# SchematicoCombinatore.net
KiCad netlist of a schematic drawn in EAGLE
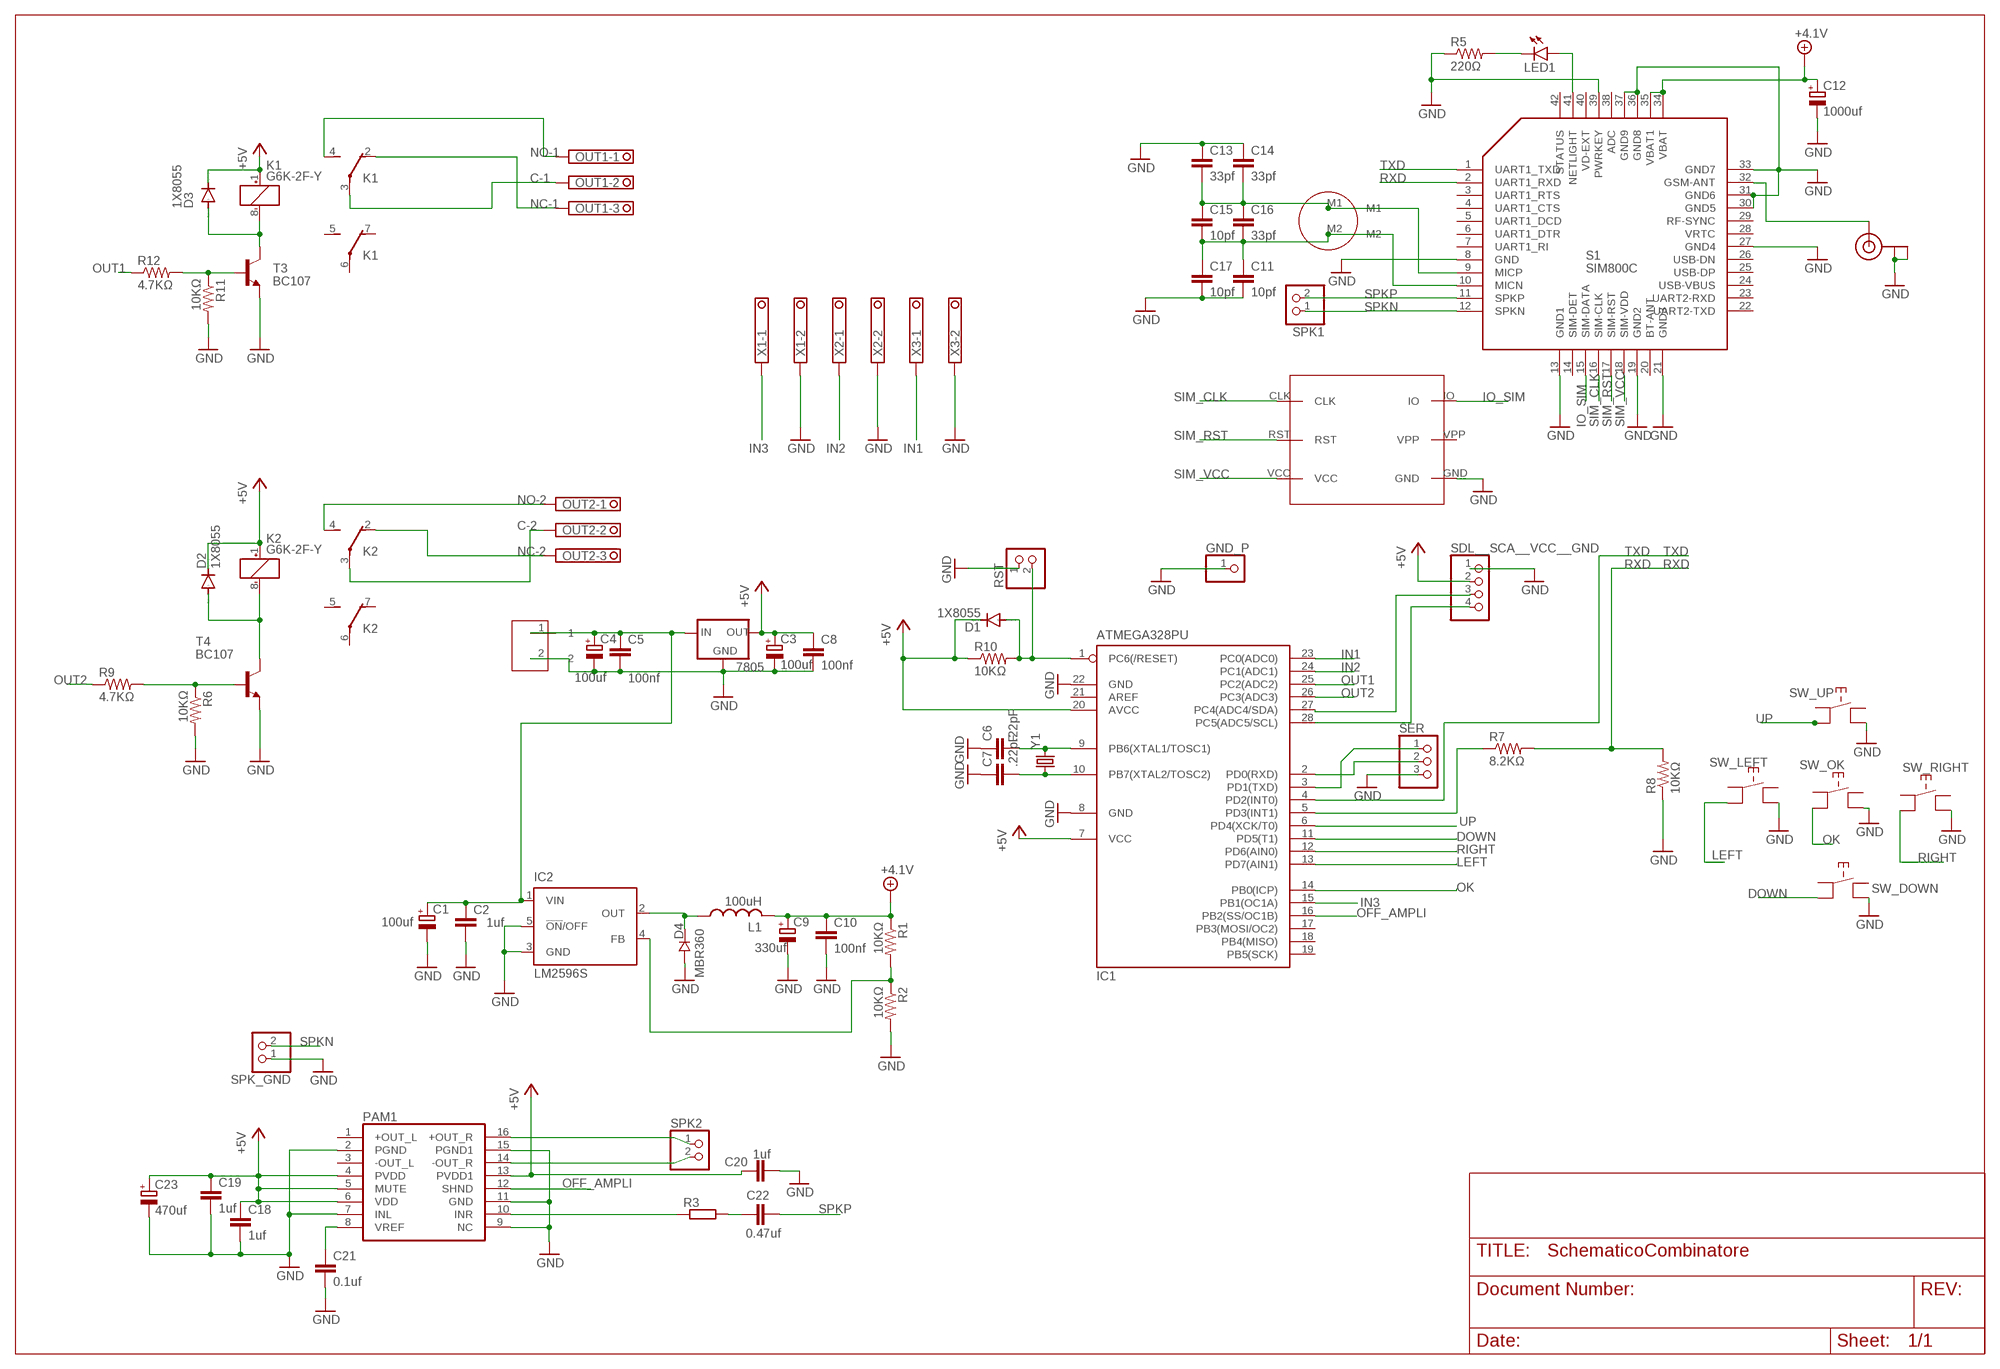
[diagram p0: schematic, sheet 1]

(export (version "E")
  (design (tool "Eeschema 10.0.6"))
  (components
    (comp (ref "7805")
      (value "7805")
      (footprint "eagle-import:78XXL")
      (libsource (lib "eagle-import") (part "V_REG_78XXSIDE"))
    )
    (comp (ref "ALIM")
      (value "CONNETTORE_ALIM")
      (footprint "eagle-import:CONNETTORE_ALIM")
      (libsource (lib "eagle-import") (part "CONNETTORE_ALIM"))
    )
    (comp (ref "C1")
      (value "100uf")
      (footprint "eagle-import:153CLV-0605")
      (libsource (lib "eagle-import") (part "CPOL-EU153CLV-0605"))
    )
    (comp (ref "C2")
      (value "1uf")
      (footprint "eagle-import:C0805")
      (libsource (lib "eagle-import") (part "C-EUC0805"))
    )
    (comp (ref "C3")
      (value "100uf")
      (footprint "eagle-import:153CLV-0605")
      (libsource (lib "eagle-import") (part "CPOL-EU153CLV-0605"))
    )
    (comp (ref "C4")
      (value "100uf")
      (footprint "eagle-import:153CLV-0605")
      (libsource (lib "eagle-import") (part "CPOL-EU153CLV-0605"))
    )
    (comp (ref "C5")
      (value "100nf")
      (footprint "eagle-import:C050-024X044")
      (libsource (lib "eagle-import") (part "C-EU050-024X044"))
    )
    (comp (ref "C6")
      (value ".22pF")
      (footprint "eagle-import:CAP-PTH-SMALL")
      (libsource (lib "eagle-import") (part "CAPPTH"))
    )
    (comp (ref "C7")
      (value ".22pF")
      (footprint "eagle-import:CAP-PTH-SMALL")
      (libsource (lib "eagle-import") (part "CAPPTH"))
    )
    (comp (ref "C8")
      (value "100nf")
      (footprint "eagle-import:C050-024X044")
      (libsource (lib "eagle-import") (part "C-EU050-024X044"))
    )
    (comp (ref "C9")
      (value "330uf")
      (footprint "eagle-import:153CLV-0605")
      (libsource (lib "eagle-import") (part "CPOL-EU153CLV-0605"))
    )
    (comp (ref "C10")
      (value "100nf")
      (footprint "eagle-import:C050-024X044")
      (libsource (lib "eagle-import") (part "C-EU050-024X044"))
    )
    (comp (ref "C11")
      (value "10pf")
      (footprint "eagle-import:C0805")
      (libsource (lib "eagle-import") (part "C-EUC0805"))
    )
    (comp (ref "C12")
      (value "1000uf")
      (footprint "eagle-import:140CLH-1014")
      (libsource (lib "eagle-import") (part "CPOL-EU140CLH-1014"))
    )
    (comp (ref "C13")
      (value "33pf")
      (footprint "eagle-import:C0805")
      (libsource (lib "eagle-import") (part "C-EUC0805"))
    )
    (comp (ref "C14")
      (value "33pf")
      (footprint "eagle-import:C0805")
      (libsource (lib "eagle-import") (part "C-EUC0805"))
    )
    (comp (ref "C15")
      (value "10pf")
      (footprint "eagle-import:C0805")
      (libsource (lib "eagle-import") (part "C-EUC0805"))
    )
    (comp (ref "C16")
      (value "33pf")
      (footprint "eagle-import:C0805")
      (libsource (lib "eagle-import") (part "C-EUC0805"))
    )
    (comp (ref "C17")
      (value "10pf")
      (footprint "eagle-import:C0805")
      (libsource (lib "eagle-import") (part "C-EUC0805"))
    )
    (comp (ref "C18")
      (value "1uf")
      (footprint "eagle-import:C0805")
      (libsource (lib "eagle-import") (part "C-EUC0805"))
    )
    (comp (ref "C19")
      (value "1uf")
      (footprint "eagle-import:C0805")
      (libsource (lib "eagle-import") (part "C-EUC0805"))
    )
    (comp (ref "C20")
      (value "1uf")
      (footprint "eagle-import:C0805")
      (libsource (lib "eagle-import") (part "C-EUC0805"))
    )
    (comp (ref "C21")
      (value "0.1uf")
      (footprint "eagle-import:C0805")
      (libsource (lib "eagle-import") (part "C-EUC0805"))
    )
    (comp (ref "C22")
      (value "0.47uf")
      (footprint "eagle-import:C0805")
      (libsource (lib "eagle-import") (part "C-EUC0805"))
    )
    (comp (ref "C23")
      (value "470uf")
      (footprint "eagle-import:153CLV-0605")
      (libsource (lib "eagle-import") (part "CPOL-EU153CLV-0605"))
    )
    (comp (ref "D1")
      (value "1X8055")
      (footprint "eagle-import:DO41-10")
      (libsource (lib "eagle-import") (part "1N4004"))
    )
    (comp (ref "D2")
      (value "1X8055")
      (footprint "eagle-import:DO41-10")
      (libsource (lib "eagle-import") (part "1N4004"))
    )
    (comp (ref "D3")
      (value "1X8055")
      (footprint "eagle-import:DO41-10")
      (libsource (lib "eagle-import") (part "1N4004"))
    )
    (comp (ref "D4")
      (value "MBR360")
      (footprint "eagle-import:SR360_DIODO_SMD")
      (libsource (lib "eagle-import") (part "MBR360"))
    )
    (comp (ref "GND_P")
      (value "PINHD-1X1")
      (footprint "eagle-import:1X01")
      (libsource (lib "eagle-import") (part "PINHD-1X1"))
    )
    (comp (ref "IC1")
      (value "ATMEGA328PU")
      (footprint "eagle-import:DIL28-3")
      (libsource (lib "eagle-import") (part "MEGA8-P"))
    )
    (comp (ref "IC2")
      (value "LM2596S")
      (footprint "eagle-import:TO263-5")
      (fields (field (name "MF") "NATIONAL SEMICONDUCTOR") (field (name "MPN") "LM2596S-ADJ/NOPB"))
      (libsource (lib "eagle-import") (part "LM2596S"))
    )
    (comp (ref "K1")
      (value "G6K-2F-Y")
      (footprint "eagle-import:G6K-2F-Y")
      (fields (field (name "MF") "OMRON COMPONENTS USA") (field (name "MPN") "G6K-2F-Y DC3"))
      (libsource (lib "eagle-import") (part "G6K-2F-Y"))
    )
    (comp (ref "K2")
      (value "G6K-2F-Y")
      (footprint "eagle-import:G6K-2F-Y")
      (fields (field (name "MF") "OMRON COMPONENTS USA") (field (name "MPN") "G6K-2F-Y DC3"))
      (libsource (lib "eagle-import") (part "G6K-2F-Y"))
    )
    (comp (ref "L1")
      (value "100uH")
      (footprint "eagle-import:0204_7")
      (libsource (lib "eagle-import") (part "L-US0204/7"))
    )
    (comp (ref "LED1")
      (value "LED3MM")
      (footprint "eagle-import:LED3MM")
      (libsource (lib "eagle-import") (part "LED3MM"))
    )
    (comp (ref "MIC2")
      (value "MICROPHONE")
      (footprint "eagle-import:MICROFONO1")
      (libsource (lib "eagle-import") (part "MICROPHONE"))
    )
    (comp (ref "OUT1")
      (value "1751251")
      (footprint "eagle-import:1751251")
      (libsource (lib "eagle-import") (part "1751251"))
    )
    (comp (ref "OUT2")
      (value "NC")
      (footprint "eagle-import:1751251")
      (libsource (lib "eagle-import") (part "1751251"))
    )
    (comp (ref "PAM1")
      (value "PAM8403")
      (footprint "eagle-import:SOP-16")
      (libsource (lib "eagle-import") (part "PAM8403"))
    )
    (comp (ref "R1")
      (value "10KΩ")
      (footprint "eagle-import:0402-RES")
      (libsource (lib "eagle-import") (part "RESISTOR0402-RES"))
    )
    (comp (ref "R2")
      (value "10KΩ")
      (footprint "eagle-import:0402-RES")
      (libsource (lib "eagle-import") (part "RESISTOR0402-RES"))
    )
    (comp (ref "R3")
      (value "R-EU_R0402")
      (footprint "eagle-import:R0402")
      (libsource (lib "eagle-import") (part "R-EU_R0402"))
    )
    (comp (ref "R5")
      (value "220Ω")
      (footprint "eagle-import:0402-RES")
      (libsource (lib "eagle-import") (part "RESISTOR0402-RES"))
    )
    (comp (ref "R6")
      (value "10KΩ")
      (footprint "eagle-import:0402-RES")
      (libsource (lib "eagle-import") (part "RESISTOR0402-RES"))
    )
    (comp (ref "R7")
      (value "8.2KΩ")
      (footprint "eagle-import:0402-RES")
      (libsource (lib "eagle-import") (part "RESISTOR0402-RES"))
    )
    (comp (ref "R8")
      (value "10KΩ")
      (footprint "eagle-import:0402-RES")
      (libsource (lib "eagle-import") (part "RESISTOR0402-RES"))
    )
    (comp (ref "R9")
      (value "4.7KΩ")
      (footprint "eagle-import:0402-RES")
      (libsource (lib "eagle-import") (part "RESISTOR0402-RES"))
    )
    (comp (ref "R10")
      (value "10KΩ")
      (footprint "eagle-import:0402-RES")
      (libsource (lib "eagle-import") (part "RESISTOR0402-RES"))
    )
    (comp (ref "R11")
      (value "10KΩ")
      (footprint "eagle-import:0402-RES")
      (libsource (lib "eagle-import") (part "RESISTOR0402-RES"))
    )
    (comp (ref "R12")
      (value "4.7KΩ")
      (footprint "eagle-import:0402-RES")
      (libsource (lib "eagle-import") (part "RESISTOR0402-RES"))
    )
    (comp (ref "RST")
      (value "PINHD-1X2")
      (footprint "eagle-import:1X02")
      (libsource (lib "eagle-import") (part "PINHD-1X2"))
    )
    (comp (ref "S1")
      (value "SIM800C")
      (footprint "eagle-import:SIM800C")
      (libsource (lib "eagle-import") (part "SIM800C"))
    )
    (comp (ref "SDL__SCA__VCC__GND")
      (value "PINHD-1X4")
      (footprint "eagle-import:1X04")
      (libsource (lib "eagle-import") (part "PINHD-1X4"))
    )
    (comp (ref "SER")
      (value "PINHD-1X3")
      (footprint "eagle-import:1X03")
      (libsource (lib "eagle-import") (part "PINHD-1X3"))
    )
    (comp (ref "SPK1")
      (value "PINHD-1X2")
      (footprint "eagle-import:1X02")
      (libsource (lib "eagle-import") (part "PINHD-1X2"))
    )
    (comp (ref "SPK2")
      (value "PINHD-1X2")
      (footprint "eagle-import:1X02")
      (libsource (lib "eagle-import") (part "PINHD-1X2"))
    )
    (comp (ref "SPK_GND")
      (value "PINHD-1X2")
      (footprint "eagle-import:1X02")
      (libsource (lib "eagle-import") (part "PINHD-1X2"))
    )
    (comp (ref "SW_DOWN")
      (value "PULSANTE_DIP_SWITCH")
      (footprint "eagle-import:PULSANTE_DIP_SWITCH")
      (libsource (lib "eagle-import") (part "PULSANTE_DIP_SWITCH"))
    )
    (comp (ref "SW_LEFT")
      (value "PULSANTE_DIP_SWITCH")
      (footprint "eagle-import:PULSANTE_DIP_SWITCH")
      (libsource (lib "eagle-import") (part "PULSANTE_DIP_SWITCH"))
    )
    (comp (ref "SW_OK")
      (value "PULSANTE_DIP_SWITCH")
      (footprint "eagle-import:PULSANTE_DIP_SWITCH")
      (libsource (lib "eagle-import") (part "PULSANTE_DIP_SWITCH"))
    )
    (comp (ref "SW_RIGHT")
      (value "PULSANTE_DIP_SWITCH")
      (footprint "eagle-import:PULSANTE_DIP_SWITCH")
      (libsource (lib "eagle-import") (part "PULSANTE_DIP_SWITCH"))
    )
    (comp (ref "SW_UP")
      (value "PULSANTE_DIP_SWITCH")
      (footprint "eagle-import:PULSANTE_DIP_SWITCH")
      (libsource (lib "eagle-import") (part "PULSANTE_DIP_SWITCH"))
    )
    (comp (ref "T3")
      (value "BC107")
      (footprint "eagle-import:TO18")
      (libsource (lib "eagle-import") (part "BC107"))
    )
    (comp (ref "T4")
      (value "BC107")
      (footprint "eagle-import:TO18")
      (libsource (lib "eagle-import") (part "BC107"))
    )
    (comp (ref "U$1")
      (value "U.FL")
      (footprint "eagle-import:U.FL")
      (libsource (lib "eagle-import") (part "U.FL"))
    )
    (comp (ref "U$2")
      (value "NANO_SIM_CARD_HOLDER")
      (footprint "eagle-import:NANO_SIM_CARD_HOLDER")
      (libsource (lib "eagle-import") (part "NANO_SIM_CARD_HOLDER"))
    )
    (comp (ref "X1")
      (value "1751248")
      (footprint "eagle-import:1751248")
      (libsource (lib "eagle-import") (part "1751248"))
    )
    (comp (ref "X2")
      (value "1751248")
      (footprint "eagle-import:1751248")
      (libsource (lib "eagle-import") (part "1751248"))
    )
    (comp (ref "X3")
      (value "1751248")
      (footprint "eagle-import:1751248")
      (libsource (lib "eagle-import") (part "1751248"))
    )
    (comp (ref "Y1")
      (value "CRYSTALHC49US")
      (footprint "eagle-import:HC49US")
      (libsource (lib "eagle-import") (part "CRYSTALHC49US"))
    )
  )
  (nets
    (net (code "1") (name "+4.1V") (class "Default")
      (node (ref "C10") (pin "1") (pinfunction "1_1") (pintype "passive"))
      (node (ref "C12") (pin "+") (pinfunction "+_+") (pintype "passive"))
      (node (ref "C9") (pin "+") (pinfunction "+_+") (pintype "passive"))
      (node (ref "L1") (pin "2") (pinfunction "2_2") (pintype "passive"))
      (node (ref "R1") (pin "1") (pinfunction "1_1") (pintype "passive"))
      (node (ref "S1") (pin "34") (pinfunction "VBAT_34") (pintype "power_in"))
      (node (ref "S1") (pin "35") (pinfunction "VBAT1_35") (pintype "power_in"))
    )
    (net (code "2") (name "+5V") (class "Default")
      (node (ref "7805") (pin "OUT") (pinfunction "OUT_OUT") (pintype "output"))
      (node (ref "C18") (pin "1") (pinfunction "1_1") (pintype "passive"))
      (node (ref "C19") (pin "1") (pinfunction "1_1") (pintype "passive"))
      (node (ref "C20") (pin "1") (pinfunction "1_1") (pintype "passive"))
      (node (ref "C23") (pin "+") (pinfunction "+_+") (pintype "passive"))
      (node (ref "C3") (pin "+") (pinfunction "+_+") (pintype "passive"))
      (node (ref "C8") (pin "1") (pinfunction "1_1") (pintype "passive"))
      (node (ref "D1") (pin "C") (pinfunction "C_C") (pintype "passive"))
      (node (ref "D2") (pin "C") (pinfunction "C_C") (pintype "passive"))
      (node (ref "D3") (pin "C") (pinfunction "C_C") (pintype "passive"))
      (node (ref "IC1") (pin "20") (pinfunction "AVCC_20") (pintype "power_in"))
      (node (ref "IC1") (pin "7") (pinfunction "VCC_7") (pintype "power_in"))
      (node (ref "K1") (pin "1") (pinfunction "+_1") (pintype "passive"))
      (node (ref "K2") (pin "1") (pinfunction "+_1") (pintype "passive"))
      (node (ref "PAM1") (pin "13") (pinfunction "PVDD1_13") (pintype "output"))
      (node (ref "PAM1") (pin "4") (pinfunction "PVDD_4") (pintype "input"))
      (node (ref "PAM1") (pin "5") (pinfunction "MUTE_5") (pintype "input"))
      (node (ref "PAM1") (pin "6") (pinfunction "VDD_6") (pintype "input"))
      (node (ref "R10") (pin "1") (pinfunction "1_1") (pintype "passive"))
      (node (ref "SDL__SCA__VCC__GND") (pin "2") (pinfunction "2_2") (pintype "passive"))
    )
    (net (code "3") (name "/C-1") (class "Default")
      (node (ref "K1") (pin "3") (pinfunction "P_3") (pintype "passive"))
      (node (ref "OUT1") (pin "2") (pinfunction "K_2") (pintype "passive"))
    )
    (net (code "4") (name "/C-2") (class "Default")
      (node (ref "K2") (pin "3") (pinfunction "P_3") (pintype "passive"))
      (node (ref "OUT2") (pin "2") (pinfunction "K_2") (pintype "passive"))
    )
    (net (code "5") (name "/DOWN") (class "Default")
      (node (ref "IC1") (pin "11") (pinfunction "PD5(T1)_11") (pintype "bidirectional"))
      (node (ref "SW_DOWN") (pin "3") (pinfunction "2_3") (pintype "bidirectional"))
    )
    (net (code "6") (name "/IN1") (class "Default")
      (node (ref "IC1") (pin "23") (pinfunction "PC0(ADC0)_23") (pintype "bidirectional"))
      (node (ref "X3") (pin "1") (pinfunction "K_1") (pintype "passive"))
    )
    (net (code "7") (name "/IN2") (class "Default")
      (node (ref "IC1") (pin "24") (pinfunction "PC1(ADC1)_24") (pintype "bidirectional"))
      (node (ref "X2") (pin "1") (pinfunction "K_1") (pintype "passive"))
    )
    (net (code "8") (name "/IN3") (class "Default")
      (node (ref "IC1") (pin "15") (pinfunction "PB1(OC1A)_15") (pintype "bidirectional"))
      (node (ref "X1") (pin "1") (pinfunction "K_1") (pintype "passive"))
    )
    (net (code "9") (name "/IO_SIM") (class "Default")
      (node (ref "S1") (pin "15") (pinfunction "SIM-DATA_15") (pintype "bidirectional"))
      (node (ref "U$2") (pin "IO") (pinfunction "IO_IO") (pintype "bidirectional"))
    )
    (net (code "10") (name "/LEFT") (class "Default")
      (node (ref "IC1") (pin "13") (pinfunction "PD7(AIN1)_13") (pintype "bidirectional"))
      (node (ref "SW_LEFT") (pin "3") (pinfunction "2_3") (pintype "bidirectional"))
    )
    (net (code "11") (name "/NC-1") (class "Default")
      (node (ref "K1") (pin "2") (pinfunction "O_2") (pintype "passive"))
      (node (ref "OUT1") (pin "3") (pinfunction "K_3") (pintype "passive"))
    )
    (net (code "12") (name "/NC-2") (class "Default")
      (node (ref "K2") (pin "2") (pinfunction "O_2") (pintype "passive"))
      (node (ref "OUT2") (pin "3") (pinfunction "K_3") (pintype "passive"))
    )
    (net (code "13") (name "/NO-1") (class "Default")
      (node (ref "K1") (pin "4") (pinfunction "S_4") (pintype "passive"))
      (node (ref "OUT1") (pin "1") (pinfunction "K_1") (pintype "passive"))
    )
    (net (code "14") (name "/NO-2") (class "Default")
      (node (ref "K2") (pin "4") (pinfunction "S_4") (pintype "passive"))
      (node (ref "OUT2") (pin "1") (pinfunction "K_1") (pintype "passive"))
    )
    (net (code "15") (name "/OFF_AMPLI") (class "Default")
      (node (ref "IC1") (pin "16") (pinfunction "PB2(SS/OC1B)_16") (pintype "bidirectional"))
      (node (ref "PAM1") (pin "12") (pinfunction "SHND_12") (pintype "output"))
    )
    (net (code "16") (name "/OK") (class "Default")
      (node (ref "IC1") (pin "14") (pinfunction "PB0(ICP)_14") (pintype "bidirectional"))
      (node (ref "SW_OK") (pin "3") (pinfunction "2_3") (pintype "bidirectional"))
    )
    (net (code "17") (name "/OUT1") (class "Default")
      (node (ref "IC1") (pin "25") (pinfunction "PC2(ADC2)_25") (pintype "bidirectional"))
      (node (ref "R12") (pin "1") (pinfunction "1_1") (pintype "passive"))
    )
    (net (code "18") (name "/OUT2") (class "Default")
      (node (ref "IC1") (pin "26") (pinfunction "PC3(ADC3)_26") (pintype "bidirectional"))
      (node (ref "R9") (pin "1") (pinfunction "1_1") (pintype "passive"))
    )
    (net (code "19") (name "/RIGHT") (class "Default")
      (node (ref "IC1") (pin "12") (pinfunction "PD6(AIN0)_12") (pintype "bidirectional"))
      (node (ref "SW_RIGHT") (pin "3") (pinfunction "2_3") (pintype "bidirectional"))
    )
    (net (code "20") (name "/RXD") (class "Default")
      (node (ref "R7") (pin "2") (pinfunction "2_2") (pintype "passive"))
      (node (ref "R8") (pin "2") (pinfunction "2_2") (pintype "passive"))
      (node (ref "S1") (pin "2") (pinfunction "UART1_RXD_2") (pintype "bidirectional"))
    )
    (net (code "21") (name "/SIM_CLK") (class "Default")
      (node (ref "S1") (pin "16") (pinfunction "SIM-CLK_16") (pintype "bidirectional"))
      (node (ref "U$2") (pin "CLK") (pinfunction "CLK_CLK") (pintype "bidirectional"))
    )
    (net (code "22") (name "/SIM_RST") (class "Default")
      (node (ref "S1") (pin "17") (pinfunction "SIM-RST_17") (pintype "bidirectional"))
      (node (ref "U$2") (pin "RST") (pinfunction "RST_RST") (pintype "bidirectional"))
    )
    (net (code "23") (name "/SIM_VCC") (class "Default")
      (node (ref "S1") (pin "18") (pinfunction "SIM-VDD_18") (pintype "bidirectional"))
      (node (ref "U$2") (pin "VCC") (pinfunction "VCC_VCC") (pintype "bidirectional"))
    )
    (net (code "24") (name "/SPKN") (class "Default")
      (node (ref "S1") (pin "12") (pinfunction "SPKN_12") (pintype "bidirectional"))
      (node (ref "SPK1") (pin "1") (pinfunction "1_1") (pintype "passive"))
      (node (ref "SPK_GND") (pin "2") (pinfunction "2_2") (pintype "passive"))
    )
    (net (code "25") (name "/SPKP") (class "Default")
      (node (ref "C22") (pin "2") (pinfunction "2_2") (pintype "passive"))
      (node (ref "S1") (pin "11") (pinfunction "SPKP_11") (pintype "bidirectional"))
      (node (ref "SPK1") (pin "2") (pinfunction "2_2") (pintype "passive"))
    )
    (net (code "26") (name "/TXD") (class "Default")
      (node (ref "IC1") (pin "4") (pinfunction "PD2(INT0)_4") (pintype "bidirectional"))
      (node (ref "S1") (pin "1") (pinfunction "UART1_TXD_1") (pintype "bidirectional"))
    )
    (net (code "27") (name "/UP") (class "Default")
      (node (ref "IC1") (pin "6") (pinfunction "PD4(XCK/T0)_6") (pintype "bidirectional"))
      (node (ref "SW_UP") (pin "3") (pinfunction "2_3") (pintype "bidirectional"))
    )
    (net (code "28") (name "GND") (class "Default")
      (node (ref "7805") (pin "GND") (pinfunction "GND_GND") (pintype "input"))
      (node (ref "ALIM") (pin "2") (pinfunction "2_2") (pintype "bidirectional"))
      (node (ref "C1") (pin "-") (pinfunction "-_-") (pintype "passive"))
      (node (ref "C10") (pin "2") (pinfunction "2_2") (pintype "passive"))
      (node (ref "C11") (pin "2") (pinfunction "2_2") (pintype "passive"))
      (node (ref "C12") (pin "-") (pinfunction "-_-") (pintype "passive"))
      (node (ref "C13") (pin "1") (pinfunction "1_1") (pintype "passive"))
      (node (ref "C14") (pin "1") (pinfunction "1_1") (pintype "passive"))
      (node (ref "C17") (pin "2") (pinfunction "2_2") (pintype "passive"))
      (node (ref "C18") (pin "2") (pinfunction "2_2") (pintype "passive"))
      (node (ref "C19") (pin "2") (pinfunction "2_2") (pintype "passive"))
      (node (ref "C2") (pin "2") (pinfunction "2_2") (pintype "passive"))
      (node (ref "C20") (pin "2") (pinfunction "2_2") (pintype "passive"))
      (node (ref "C21") (pin "2") (pinfunction "2_2") (pintype "passive"))
      (node (ref "C23") (pin "-") (pinfunction "-_-") (pintype "passive"))
      (node (ref "C3") (pin "-") (pinfunction "-_-") (pintype "passive"))
      (node (ref "C4") (pin "-") (pinfunction "-_-") (pintype "passive"))
      (node (ref "C5") (pin "2") (pinfunction "2_2") (pintype "passive"))
      (node (ref "C6") (pin "1") (pinfunction "1_1") (pintype "passive"))
      (node (ref "C7") (pin "1") (pinfunction "1_1") (pintype "passive"))
      (node (ref "C8") (pin "2") (pinfunction "2_2") (pintype "passive"))
      (node (ref "C9") (pin "-") (pinfunction "-_-") (pintype "passive"))
      (node (ref "D4") (pin "P$1") (pinfunction "P$1_P$1") (pintype "bidirectional"))
      (node (ref "GND_P") (pin "1") (pinfunction "1_1") (pintype "passive"))
      (node (ref "IC1") (pin "22") (pinfunction "GND_22") (pintype "power_in"))
      (node (ref "IC1") (pin "8") (pinfunction "GND_8") (pintype "power_in"))
      (node (ref "IC2") (pin "3") (pinfunction "GND_3") (pintype "power_in"))
      (node (ref "IC2") (pin "5") (pinfunction "~{ON}/OFF_5") (pintype "input"))
      (node (ref "PAM1") (pin "11") (pinfunction "GND_11") (pintype "output"))
      (node (ref "PAM1") (pin "15") (pinfunction "PGND1_15") (pintype "output"))
      (node (ref "PAM1") (pin "2") (pinfunction "PGND_2") (pintype "input"))
      (node (ref "PAM1") (pin "7") (pinfunction "INL_7") (pintype "input"))
      (node (ref "PAM1") (pin "9") (pinfunction "NC_9") (pintype "output"))
      (node (ref "R11") (pin "2") (pinfunction "2_2") (pintype "passive"))
      (node (ref "R2") (pin "2") (pinfunction "2_2") (pintype "passive"))
      (node (ref "R5") (pin "1") (pinfunction "1_1") (pintype "passive"))
      (node (ref "R6") (pin "2") (pinfunction "2_2") (pintype "passive"))
      (node (ref "R8") (pin "1") (pinfunction "1_1") (pintype "passive"))
      (node (ref "RST") (pin "1") (pinfunction "1_1") (pintype "passive"))
      (node (ref "S1") (pin "13") (pinfunction "GND1_13") (pintype "power_in"))
      (node (ref "S1") (pin "19") (pinfunction "GND2_19") (pintype "power_in"))
      (node (ref "S1") (pin "21") (pinfunction "GND3_21") (pintype "power_in"))
      (node (ref "S1") (pin "27") (pinfunction "GND4_27") (pintype "power_in"))
      (node (ref "S1") (pin "30") (pinfunction "GND5_30") (pintype "power_in"))
      (node (ref "S1") (pin "31") (pinfunction "GND6_31") (pintype "power_in"))
      (node (ref "S1") (pin "33") (pinfunction "GND7_33") (pintype "power_in"))
      (node (ref "S1") (pin "36") (pinfunction "GND8_36") (pintype "power_in"))
      (node (ref "S1") (pin "37") (pinfunction "GND9_37") (pintype "power_in"))
      (node (ref "S1") (pin "39") (pinfunction "PWRKEY_39") (pintype "bidirectional"))
      (node (ref "S1") (pin "8") (pinfunction "GND_8") (pintype "power_in"))
      (node (ref "SDL__SCA__VCC__GND") (pin "1") (pinfunction "1_1") (pintype "passive"))
      (node (ref "SER") (pin "3") (pinfunction "3_3") (pintype "passive"))
      (node (ref "SPK_GND") (pin "1") (pinfunction "1_1") (pintype "passive"))
      (node (ref "SW_DOWN") (pin "1") (pinfunction "4_1") (pintype "bidirectional"))
      (node (ref "SW_LEFT") (pin "1") (pinfunction "4_1") (pintype "bidirectional"))
      (node (ref "SW_OK") (pin "1") (pinfunction "4_1") (pintype "bidirectional"))
      (node (ref "SW_RIGHT") (pin "1") (pinfunction "4_1") (pintype "bidirectional"))
      (node (ref "SW_UP") (pin "1") (pinfunction "4_1") (pintype "bidirectional"))
      (node (ref "T3") (pin "1") (pinfunction "E_1") (pintype "passive"))
      (node (ref "T4") (pin "1") (pinfunction "E_1") (pintype "passive"))
      (node (ref "U$1") (pin "1") (pinfunction "GND_1") (pintype "passive"))
      (node (ref "U$1") (pin "2") (pinfunction "GND_2") (pintype "passive"))
      (node (ref "U$2") (pin "GND") (pinfunction "GND_GND") (pintype "bidirectional"))
      (node (ref "X1") (pin "2") (pinfunction "K_2") (pintype "passive"))
      (node (ref "X2") (pin "2") (pinfunction "K_2") (pintype "passive"))
      (node (ref "X3") (pin "2") (pinfunction "K_2") (pintype "passive"))
    )
    (net (code "29") (name "Net-(C22-Pad1)") (class "Default")
      (node (ref "C22") (pin "1") (pinfunction "1_1") (pintype "passive"))
      (node (ref "R3") (pin "2") (pinfunction "2_2") (pintype "passive"))
    )
    (net (code "30") (name "Net-(IC1-PB6(XTAL1{slash}TOSC1))") (class "Default")
      (node (ref "C6") (pin "2") (pinfunction "2_2") (pintype "passive"))
      (node (ref "IC1") (pin "9") (pinfunction "PB6(XTAL1/TOSC1)_9") (pintype "bidirectional"))
      (node (ref "Y1") (pin "2") (pinfunction "2_2") (pintype "passive"))
    )
    (net (code "31") (name "Net-(IC1-PB7(XTAL2{slash}TOSC2))") (class "Default")
      (node (ref "C7") (pin "2") (pinfunction "2_2") (pintype "passive"))
      (node (ref "IC1") (pin "10") (pinfunction "PB7(XTAL2/TOSC2)_10") (pintype "bidirectional"))
      (node (ref "Y1") (pin "1") (pinfunction "1_1") (pintype "passive"))
    )
    (net (code "32") (name "Net-(IC1-PC4(ADC4{slash}SDA))") (class "Default")
      (node (ref "IC1") (pin "27") (pinfunction "PC4(ADC4/SDA)_27") (pintype "bidirectional"))
      (node (ref "SDL__SCA__VCC__GND") (pin "3") (pinfunction "3_3") (pintype "passive"))
    )
    (net (code "33") (name "Net-(IC1-PC5(ADC5{slash}SCL))") (class "Default")
      (node (ref "IC1") (pin "28") (pinfunction "PC5(ADC5/SCL)_28") (pintype "bidirectional"))
      (node (ref "SDL__SCA__VCC__GND") (pin "4") (pinfunction "4_4") (pintype "passive"))
    )
    (net (code "34") (name "Net-(IC1-PC6({slash}RESET))") (class "Default")
      (node (ref "D1") (pin "A") (pinfunction "A_A") (pintype "passive"))
      (node (ref "IC1") (pin "1") (pinfunction "PC6(/RESET)_1") (pintype "bidirectional"))
      (node (ref "R10") (pin "2") (pinfunction "2_2") (pintype "passive"))
      (node (ref "RST") (pin "2") (pinfunction "2_2") (pintype "passive"))
    )
    (net (code "35") (name "Net-(IC1-PD0(RXD))") (class "Default")
      (node (ref "IC1") (pin "2") (pinfunction "PD0(RXD)_2") (pintype "bidirectional"))
      (node (ref "SER") (pin "2") (pinfunction "2_2") (pintype "passive"))
    )
    (net (code "36") (name "Net-(IC1-PD1(TXD))") (class "Default")
      (node (ref "IC1") (pin "3") (pinfunction "PD1(TXD)_3") (pintype "bidirectional"))
      (node (ref "SER") (pin "1") (pinfunction "1_1") (pintype "passive"))
    )
    (net (code "37") (name "Net-(IC1-PD3(INT1))") (class "Default")
      (node (ref "IC1") (pin "5") (pinfunction "PD3(INT1)_5") (pintype "bidirectional"))
      (node (ref "R7") (pin "1") (pinfunction "1_1") (pintype "passive"))
    )
    (net (code "38") (name "Net-(IC2-FB)") (class "Default")
      (node (ref "IC2") (pin "4") (pinfunction "FB_4") (pintype "input"))
      (node (ref "R1") (pin "2") (pinfunction "2_2") (pintype "passive"))
      (node (ref "R2") (pin "1") (pinfunction "1_1") (pintype "passive"))
    )
    (net (code "39") (name "Net-(IC2-OUT)") (class "Default")
      (node (ref "D4") (pin "P$2") (pinfunction "P$2_P$2") (pintype "bidirectional"))
      (node (ref "IC2") (pin "2") (pinfunction "OUT_2") (pintype "output"))
      (node (ref "L1") (pin "1") (pinfunction "1_1") (pintype "passive"))
    )
    (net (code "40") (name "Net-(IC2-VIN)") (class "Default")
      (node (ref "7805") (pin "IN") (pinfunction "IN_IN") (pintype "input"))
      (node (ref "ALIM") (pin "1") (pinfunction "1_1") (pintype "bidirectional"))
      (node (ref "C1") (pin "+") (pinfunction "+_+") (pintype "passive"))
      (node (ref "C2") (pin "1") (pinfunction "1_1") (pintype "passive"))
      (node (ref "C4") (pin "+") (pinfunction "+_+") (pintype "passive"))
      (node (ref "C5") (pin "1") (pinfunction "1_1") (pintype "passive"))
      (node (ref "IC2") (pin "1") (pinfunction "VIN_1") (pintype "input"))
    )
    (net (code "41") (name "Net-(K1A--)") (class "Default")
      (node (ref "D3") (pin "A") (pinfunction "A_A") (pintype "passive"))
      (node (ref "K1") (pin "8") (pinfunction "-_8") (pintype "passive"))
      (node (ref "T3") (pin "3") (pinfunction "C_3") (pintype "passive"))
    )
    (net (code "42") (name "Net-(K2A--)") (class "Default")
      (node (ref "D2") (pin "A") (pinfunction "A_A") (pintype "passive"))
      (node (ref "K2") (pin "8") (pinfunction "-_8") (pintype "passive"))
      (node (ref "T4") (pin "3") (pinfunction "C_3") (pintype "passive"))
    )
    (net (code "43") (name "Net-(LED1-C)") (class "Default")
      (node (ref "LED1") (pin "K") (pinfunction "C_K") (pintype "passive"))
      (node (ref "R5") (pin "2") (pinfunction "2_2") (pintype "passive"))
    )
    (net (code "44") (name "Net-(PAM1-+OUT_R)") (class "Default")
      (node (ref "PAM1") (pin "16") (pinfunction "+OUT_R_16") (pintype "output"))
      (node (ref "SPK2") (pin "1") (pinfunction "1_1") (pintype "passive"))
    )
    (net (code "45") (name "Net-(PAM1--OUT_R)") (class "Default")
      (node (ref "PAM1") (pin "14") (pinfunction "-OUT_R_14") (pintype "output"))
      (node (ref "SPK2") (pin "2") (pinfunction "2_2") (pintype "passive"))
    )
    (net (code "46") (name "Net-(PAM1-INR)") (class "Default")
      (node (ref "PAM1") (pin "10") (pinfunction "INR_10") (pintype "output"))
      (node (ref "R3") (pin "1") (pinfunction "1_1") (pintype "passive"))
    )
    (net (code "47") (name "Net-(PAM1-VREF)") (class "Default")
      (node (ref "C21") (pin "1") (pinfunction "1_1") (pintype "passive"))
      (node (ref "PAM1") (pin "8") (pinfunction "VREF_8") (pintype "input"))
    )
    (net (code "48") (name "Net-(S1-GSM-ANT)") (class "Default")
      (node (ref "S1") (pin "32") (pinfunction "GSM-ANT_32") (pintype "bidirectional"))
      (node (ref "U$1") (pin "3") (pinfunction "SIGNAL_3") (pintype "passive"))
    )
    (net (code "49") (name "Net-(S1-MICN)") (class "Default")
      (node (ref "C11") (pin "1") (pinfunction "1_1") (pintype "passive"))
      (node (ref "C15") (pin "2") (pinfunction "2_2") (pintype "passive"))
      (node (ref "C16") (pin "2") (pinfunction "2_2") (pintype "passive"))
      (node (ref "C17") (pin "1") (pinfunction "1_1") (pintype "passive"))
      (node (ref "MIC2") (pin "M2") (pinfunction "M2_M2") (pintype "bidirectional"))
      (node (ref "S1") (pin "10") (pinfunction "MICN_10") (pintype "bidirectional"))
    )
    (net (code "50") (name "Net-(S1-MICP)") (class "Default")
      (node (ref "C13") (pin "2") (pinfunction "2_2") (pintype "passive"))
      (node (ref "C14") (pin "2") (pinfunction "2_2") (pintype "passive"))
      (node (ref "C15") (pin "1") (pinfunction "1_1") (pintype "passive"))
      (node (ref "C16") (pin "1") (pinfunction "1_1") (pintype "passive"))
      (node (ref "MIC2") (pin "M1") (pinfunction "M1_M1") (pintype "bidirectional"))
      (node (ref "S1") (pin "9") (pinfunction "MICP_9") (pintype "bidirectional"))
    )
    (net (code "51") (name "Net-(S1-NETLIGHT)") (class "Default")
      (node (ref "LED1") (pin "A") (pinfunction "A_A") (pintype "passive"))
      (node (ref "S1") (pin "41") (pinfunction "NETLIGHT_41") (pintype "bidirectional"))
    )
    (net (code "52") (name "Net-(T3-B)") (class "Default")
      (node (ref "R11") (pin "1") (pinfunction "1_1") (pintype "passive"))
      (node (ref "R12") (pin "2") (pinfunction "2_2") (pintype "passive"))
      (node (ref "T3") (pin "2") (pinfunction "B_2") (pintype "passive"))
    )
    (net (code "53") (name "Net-(T4-B)") (class "Default")
      (node (ref "R6") (pin "1") (pinfunction "1_1") (pintype "passive"))
      (node (ref "R9") (pin "2") (pinfunction "2_2") (pintype "passive"))
      (node (ref "T4") (pin "2") (pinfunction "B_2") (pintype "passive"))
    )
    (net (code "54") (name "unconnected-(IC1-AREF-Pad21)") (class "Default")
      (node (ref "IC1") (pin "21") (pinfunction "AREF_21") (pintype "passive"))
    )
    (net (code "55") (name "unconnected-(IC1-PB3(MOSI{slash}OC2)-Pad17)") (class "Default")
      (node (ref "IC1") (pin "17") (pinfunction "PB3(MOSI/OC2)_17") (pintype "bidirectional"))
    )
    (net (code "56") (name "unconnected-(IC1-PB4(MISO)-Pad18)") (class "Default")
      (node (ref "IC1") (pin "18") (pinfunction "PB4(MISO)_18") (pintype "bidirectional"))
    )
    (net (code "57") (name "unconnected-(IC1-PB5(SCK)-Pad19)") (class "Default")
      (node (ref "IC1") (pin "19") (pinfunction "PB5(SCK)_19") (pintype "bidirectional"))
    )
    (net (code "58") (name "unconnected-(K1C-O-Pad7)") (class "Default")
      (node (ref "K1") (pin "7") (pinfunction "O_7") (pintype "passive"))
    )
    (net (code "59") (name "unconnected-(K1C-P-Pad6)") (class "Default")
      (node (ref "K1") (pin "6") (pinfunction "P_6") (pintype "passive"))
    )
    (net (code "60") (name "unconnected-(K1C-S-Pad5)") (class "Default")
      (node (ref "K1") (pin "5") (pinfunction "S_5") (pintype "passive"))
    )
    (net (code "61") (name "unconnected-(K2C-O-Pad7)") (class "Default")
      (node (ref "K2") (pin "7") (pinfunction "O_7") (pintype "passive"))
    )
    (net (code "62") (name "unconnected-(K2C-P-Pad6)") (class "Default")
      (node (ref "K2") (pin "6") (pinfunction "P_6") (pintype "passive"))
    )
    (net (code "63") (name "unconnected-(K2C-S-Pad5)") (class "Default")
      (node (ref "K2") (pin "5") (pinfunction "S_5") (pintype "passive"))
    )
    (net (code "64") (name "unconnected-(PAM1-+OUT_L-Pad1)") (class "Default")
      (node (ref "PAM1") (pin "1") (pinfunction "+OUT_L_1") (pintype "input"))
    )
    (net (code "65") (name "unconnected-(PAM1--OUT_L-Pad3)") (class "Default")
      (node (ref "PAM1") (pin "3") (pinfunction "-OUT_L_3") (pintype "input"))
    )
    (net (code "66") (name "unconnected-(S1-ADC-Pad38)") (class "Default")
      (node (ref "S1") (pin "38") (pinfunction "ADC_38") (pintype "bidirectional"))
    )
    (net (code "67") (name "unconnected-(S1-BT-ANT-Pad20)") (class "Default")
      (node (ref "S1") (pin "20") (pinfunction "BT-ANT_20") (pintype "bidirectional"))
    )
    (net (code "68") (name "unconnected-(S1-RF-SYNC-Pad29)") (class "Default")
      (node (ref "S1") (pin "29") (pinfunction "RF-SYNC_29") (pintype "bidirectional"))
    )
    (net (code "69") (name "unconnected-(S1-SIM-DET-Pad14)") (class "Default")
      (node (ref "S1") (pin "14") (pinfunction "SIM-DET_14") (pintype "bidirectional"))
    )
    (net (code "70") (name "unconnected-(S1-STATUS-Pad42)") (class "Default")
      (node (ref "S1") (pin "42") (pinfunction "STATUS_42") (pintype "bidirectional"))
    )
    (net (code "71") (name "unconnected-(S1-UART1_CTS-Pad4)") (class "Default")
      (node (ref "S1") (pin "4") (pinfunction "UART1_CTS_4") (pintype "bidirectional"))
    )
    (net (code "72") (name "unconnected-(S1-UART1_DCD-Pad5)") (class "Default")
      (node (ref "S1") (pin "5") (pinfunction "UART1_DCD_5") (pintype "bidirectional"))
    )
    (net (code "73") (name "unconnected-(S1-UART1_DTR-Pad6)") (class "Default")
      (node (ref "S1") (pin "6") (pinfunction "UART1_DTR_6") (pintype "bidirectional"))
    )
    (net (code "74") (name "unconnected-(S1-UART1_RI-Pad7)") (class "Default")
      (node (ref "S1") (pin "7") (pinfunction "UART1_RI_7") (pintype "bidirectional"))
    )
    (net (code "75") (name "unconnected-(S1-UART1_RTS-Pad3)") (class "Default")
      (node (ref "S1") (pin "3") (pinfunction "UART1_RTS_3") (pintype "bidirectional"))
    )
    (net (code "76") (name "unconnected-(S1-UART2-RXD-Pad23)") (class "Default")
      (node (ref "S1") (pin "23") (pinfunction "UART2-RXD_23") (pintype "bidirectional"))
    )
    (net (code "77") (name "unconnected-(S1-UART2-TXD-Pad22)") (class "Default")
      (node (ref "S1") (pin "22") (pinfunction "UART2-TXD_22") (pintype "bidirectional"))
    )
    (net (code "78") (name "unconnected-(S1-USB-DN-Pad26)") (class "Default")
      (node (ref "S1") (pin "26") (pinfunction "USB-DN_26") (pintype "bidirectional"))
    )
    (net (code "79") (name "unconnected-(S1-USB-DP-Pad25)") (class "Default")
      (node (ref "S1") (pin "25") (pinfunction "USB-DP_25") (pintype "bidirectional"))
    )
    (net (code "80") (name "unconnected-(S1-USB-VBUS-Pad24)") (class "Default")
      (node (ref "S1") (pin "24") (pinfunction "USB-VBUS_24") (pintype "bidirectional"))
    )
    (net (code "81") (name "unconnected-(S1-VD-EXT-Pad40)") (class "Default")
      (node (ref "S1") (pin "40") (pinfunction "VD-EXT_40") (pintype "bidirectional"))
    )
    (net (code "82") (name "unconnected-(S1-VRTC-Pad28)") (class "Default")
      (node (ref "S1") (pin "28") (pinfunction "VRTC_28") (pintype "bidirectional"))
    )
    (net (code "83") (name "unconnected-(SW_DOWN-1-Pad4)") (class "Default")
      (node (ref "SW_DOWN") (pin "4") (pinfunction "1_4") (pintype "bidirectional"))
    )
    (net (code "84") (name "unconnected-(SW_DOWN-3-Pad2)") (class "Default")
      (node (ref "SW_DOWN") (pin "2") (pinfunction "3_2") (pintype "bidirectional"))
    )
    (net (code "85") (name "unconnected-(SW_LEFT-1-Pad4)") (class "Default")
      (node (ref "SW_LEFT") (pin "4") (pinfunction "1_4") (pintype "bidirectional"))
    )
    (net (code "86") (name "unconnected-(SW_LEFT-3-Pad2)") (class "Default")
      (node (ref "SW_LEFT") (pin "2") (pinfunction "3_2") (pintype "bidirectional"))
    )
    (net (code "87") (name "unconnected-(SW_OK-1-Pad4)") (class "Default")
      (node (ref "SW_OK") (pin "4") (pinfunction "1_4") (pintype "bidirectional"))
    )
    (net (code "88") (name "unconnected-(SW_OK-3-Pad2)") (class "Default")
      (node (ref "SW_OK") (pin "2") (pinfunction "3_2") (pintype "bidirectional"))
    )
    (net (code "89") (name "unconnected-(SW_RIGHT-1-Pad4)") (class "Default")
      (node (ref "SW_RIGHT") (pin "4") (pinfunction "1_4") (pintype "bidirectional"))
    )
    (net (code "90") (name "unconnected-(SW_RIGHT-3-Pad2)") (class "Default")
      (node (ref "SW_RIGHT") (pin "2") (pinfunction "3_2") (pintype "bidirectional"))
    )
    (net (code "91") (name "unconnected-(SW_UP-1-Pad4)") (class "Default")
      (node (ref "SW_UP") (pin "4") (pinfunction "1_4") (pintype "bidirectional"))
    )
    (net (code "92") (name "unconnected-(SW_UP-3-Pad2)") (class "Default")
      (node (ref "SW_UP") (pin "2") (pinfunction "3_2") (pintype "bidirectional"))
    )
    (net (code "93") (name "unconnected-(U$2-PadVPP)") (class "Default")
      (node (ref "U$2") (pin "VPP") (pinfunction "VPP_VPP") (pintype "bidirectional"))
    )
  )
)
